# Drone_v1_0.net
KiCad netlist of a schematic drawn in Altium Designer
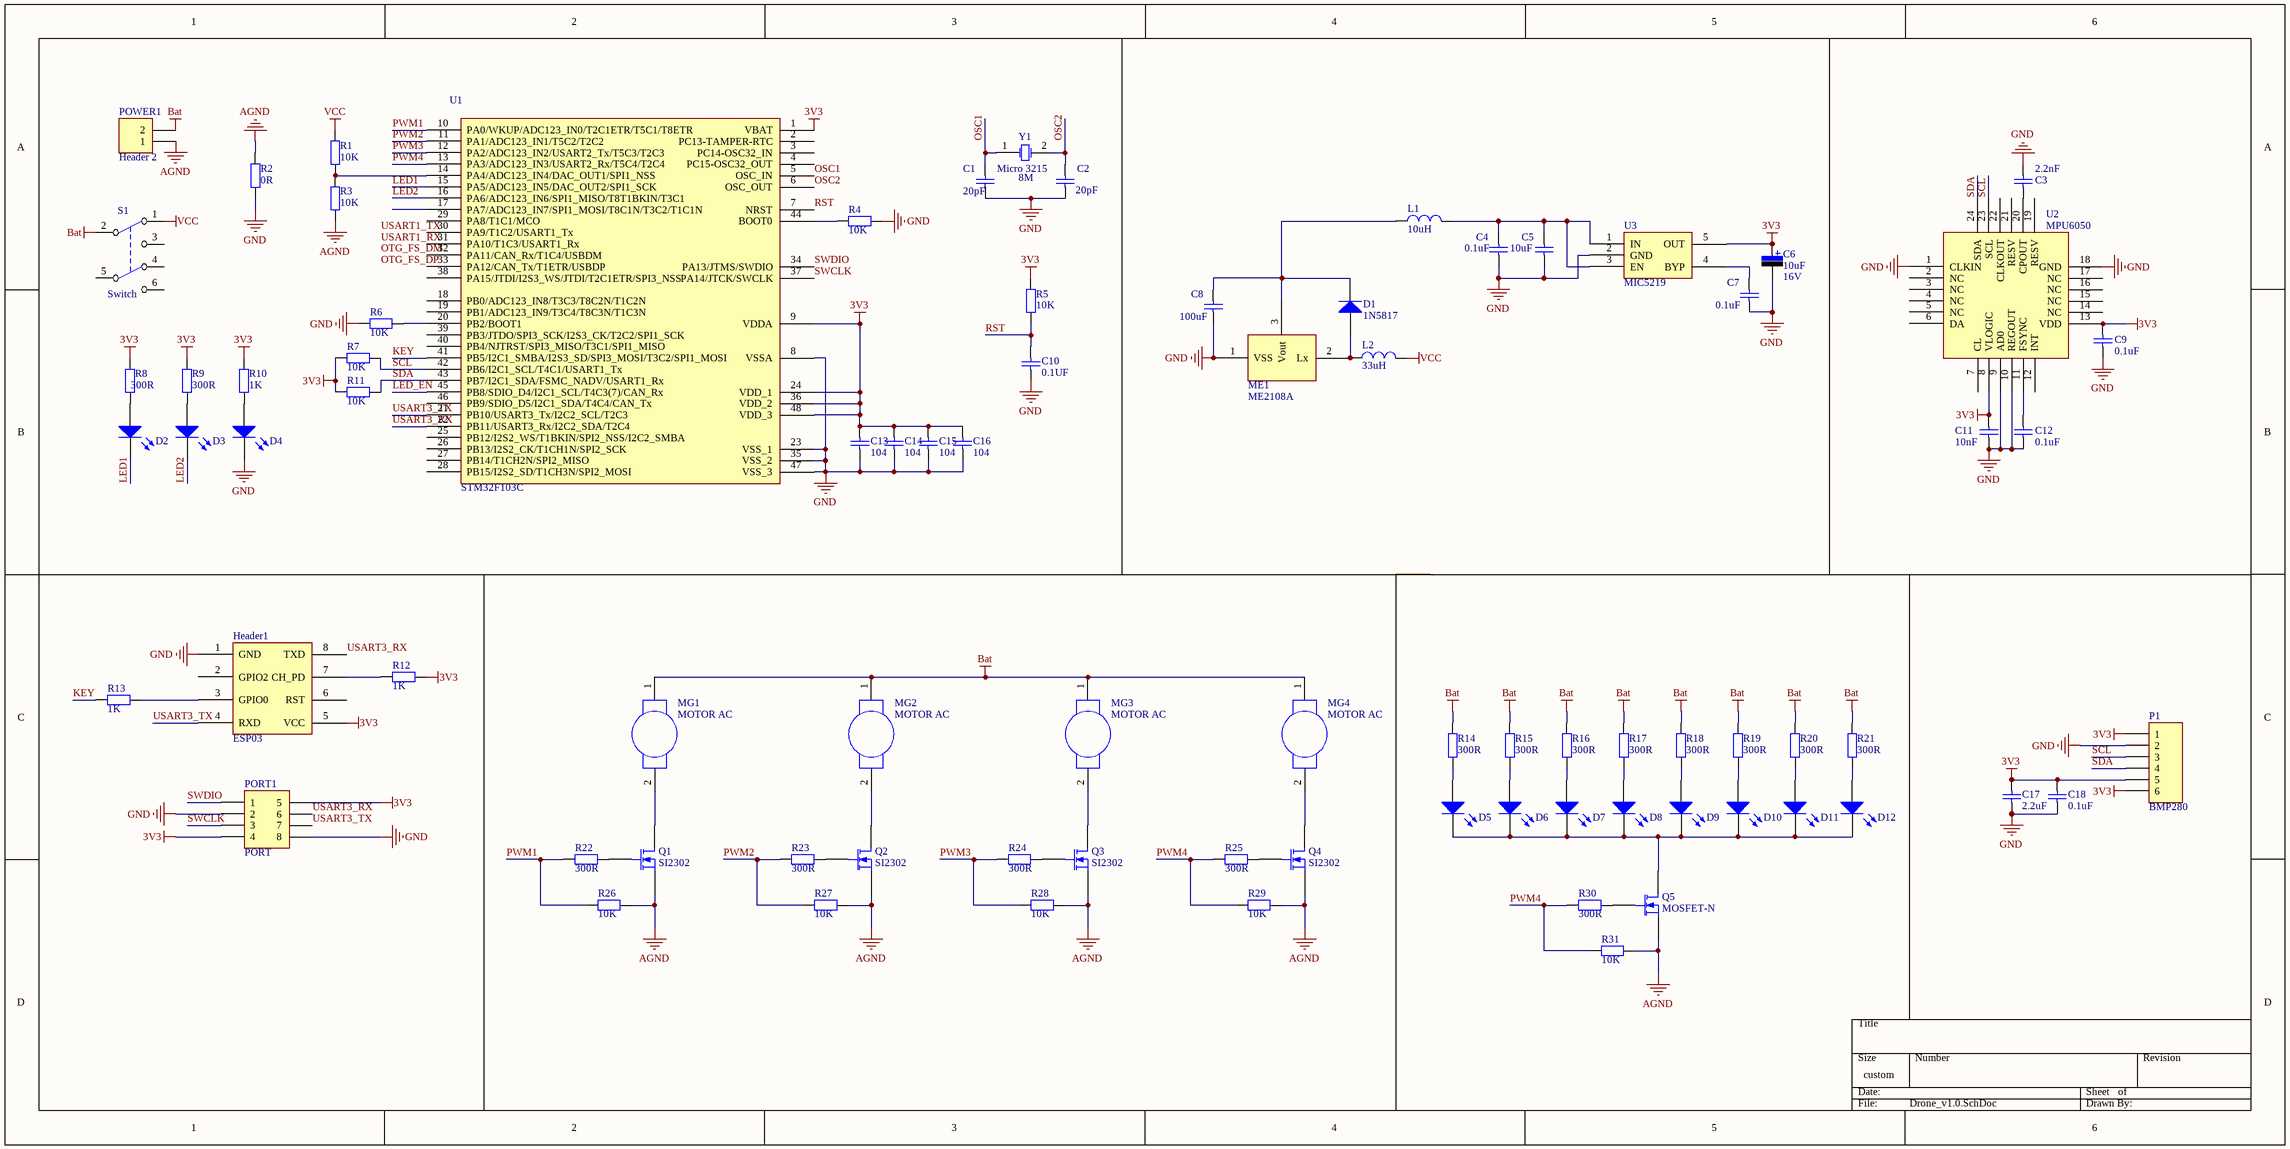
[diagram p0: Drone_v1.0.SchDoc]

(export (version "E")
  (design (tool "Eeschema 10.0.6"))
  (components
    (comp (ref "C1")
      (value "20pF")
      (footprint "0805-2")
      (description "Capacitor")
      (fields (field (name "Comment") "0402 12pF") (field (name "PUBLISHER") "Altium Limited"))
      (libsource (lib "Miscellaneous Devices") (part "Cap"))
    )
    (comp (ref "C2")
      (value "20pF")
      (footprint "0805-2")
      (description "Capacitor")
      (fields (field (name "Comment") "0402 12pF") (field (name "PUBLISHER") "Altium Limited"))
      (libsource (lib "Miscellaneous Devices") (part "Cap"))
    )
    (comp (ref "C3")
      (value "0402 12pF")
      (footprint "0805-2")
      (description "Capacitor")
      (fields (field (name "50V") "2.2nF") (field (name "PUBLISHER") "Altium Limited"))
      (libsource (lib "Miscellaneous Devices") (part "Cap"))
    )
    (comp (ref "C4")
      (value "0.1uF")
      (footprint "0805-2")
      (description "Capacitor")
      (fields (field (name "Comment") "0402 12pF") (field (name "PUBLISHER") "Altium Limited"))
      (libsource (lib "Miscellaneous Devices") (part "Cap"))
    )
    (comp (ref "C5")
      (value "10uF")
      (footprint "0805-2")
      (description "Capacitor")
      (fields (field (name "Comment") "0402 12pF") (field (name "PUBLISHER") "Altium Limited"))
      (libsource (lib "Miscellaneous Devices") (part "Cap"))
    )
    (comp (ref "C6")
      (value "10uF")
      (footprint "1206")
      (description "极性电解电容")
      (fields
        (field (name "VOL") "16V")
        (field (name "Comment") "Cap Pol")
        (field (name "PUBLISHER") "Altium Limited")
      )
      (libsource (lib "Fszhang") (part "Cap Pol"))
    )
    (comp (ref "C7")
      (value "0402 12pF")
      (footprint "0805-2")
      (description "Capacitor")
      (fields (field (name "50V") "0.1uF") (field (name "PUBLISHER") "Altium Limited"))
      (libsource (lib "Miscellaneous Devices") (part "Cap"))
    )
    (comp (ref "C8")
      (value "100uF")
      (footprint "0805-2")
      (description "Capacitor")
      (fields (field (name "Comment") "0402 12pF") (field (name "PUBLISHER") "Altium Limited"))
      (libsource (lib "Miscellaneous Devices") (part "Cap"))
    )
    (comp (ref "C9")
      (value "0402 12pF")
      (footprint "0805-2")
      (description "Capacitor")
      (fields (field (name "50V") "0.1uF") (field (name "PUBLISHER") "Altium Limited"))
      (libsource (lib "Miscellaneous Devices") (part "Cap"))
    )
    (comp (ref "C10")
      (value "0.1UF")
      (footprint "0805-2")
      (description "无极性电容")
      (fields (field (name "Comment") "Cap") (field (name "PUBLISHER") "Altium Limited"))
      (libsource (lib "Fszhang") (part "Cap"))
    )
    (comp (ref "C11")
      (value "0402 12pF")
      (footprint "0805-2")
      (description "Capacitor")
      (fields (field (name "50V") "10nF") (field (name "PUBLISHER") "Altium Limited"))
      (libsource (lib "Miscellaneous Devices") (part "Cap"))
    )
    (comp (ref "C12")
      (value "0402 12pF")
      (footprint "0805-2")
      (description "Capacitor")
      (fields (field (name "50V") "0.1uF") (field (name "PUBLISHER") "Altium Limited"))
      (libsource (lib "Miscellaneous Devices") (part "Cap"))
    )
    (comp (ref "C13")
      (value "104")
      (footprint "0805-2")
      (description "无极性电容")
      (fields (field (name "Comment") "Cap") (field (name "PUBLISHER") "Altium Limited"))
      (libsource (lib "Fszhang") (part "Cap"))
    )
    (comp (ref "C14")
      (value "104")
      (footprint "0805-2")
      (description "无极性电容")
      (fields (field (name "Comment") "Cap") (field (name "PUBLISHER") "Altium Limited"))
      (libsource (lib "Fszhang") (part "Cap"))
    )
    (comp (ref "C15")
      (value "104")
      (footprint "0805-2")
      (description "无极性电容")
      (fields (field (name "Comment") "Cap") (field (name "PUBLISHER") "Altium Limited"))
      (libsource (lib "Fszhang") (part "Cap"))
    )
    (comp (ref "C16")
      (value "104")
      (footprint "0805-2")
      (description "无极性电容")
      (fields (field (name "Comment") "Cap") (field (name "PUBLISHER") "Altium Limited"))
      (libsource (lib "Fszhang") (part "Cap"))
    )
    (comp (ref "C17")
      (value "0402 12pF")
      (footprint "0805-2")
      (description "Capacitor")
      (fields (field (name "50V") "2.2uF") (field (name "PUBLISHER") "Altium Limited"))
      (libsource (lib "Miscellaneous Devices") (part "Cap"))
    )
    (comp (ref "C18")
      (value "0402 12pF")
      (footprint "0805-2")
      (description "Capacitor")
      (fields (field (name "50V") "0.1uF") (field (name "PUBLISHER") "Altium Limited"))
      (libsource (lib "Miscellaneous Devices") (part "Cap"))
    )
    (comp (ref "D1")
      (value "Diode")
      (footprint "DIODE-1206")
      (description "二极管")
      (fields (field (name "TYPE") "1N5817") (field (name "PUBLISHER") "Altium Limited"))
      (libsource (lib "Fszhang") (part "Diode"))
    )
    (comp (ref "D2")
      (value "LED0")
      (footprint "LED_0805")
      (description "发光二极管")
      (fields (field (name "PUBLISHER") "Altium Limited"))
      (libsource (lib "Fszhang") (part "LED0"))
    )
    (comp (ref "D3")
      (value "LED0")
      (footprint "LED_0805")
      (description "发光二极管")
      (fields (field (name "PUBLISHER") "Altium Limited"))
      (libsource (lib "Fszhang") (part "LED0"))
    )
    (comp (ref "D4")
      (value "LED0")
      (footprint "LED_0805")
      (description "发光二极管")
      (fields (field (name "PUBLISHER") "Altium Limited"))
      (libsource (lib "Fszhang") (part "LED0"))
    )
    (comp (ref "D5")
      (value "LED0")
      (footprint "LED_0805")
      (description "发光二极管")
      (fields (field (name "PUBLISHER") "Altium Limited"))
      (libsource (lib "Fszhang") (part "LED0"))
    )
    (comp (ref "D6")
      (value "LED0")
      (footprint "LED_0805")
      (description "发光二极管")
      (fields (field (name "PUBLISHER") "Altium Limited"))
      (libsource (lib "Fszhang") (part "LED0"))
    )
    (comp (ref "D7")
      (value "LED0")
      (footprint "LED_0805")
      (description "发光二极管")
      (fields (field (name "PUBLISHER") "Altium Limited"))
      (libsource (lib "Fszhang") (part "LED0"))
    )
    (comp (ref "D8")
      (value "LED0")
      (footprint "LED_0805")
      (description "发光二极管")
      (fields (field (name "PUBLISHER") "Altium Limited"))
      (libsource (lib "Fszhang") (part "LED0"))
    )
    (comp (ref "D9")
      (value "LED0")
      (footprint "LED_0805")
      (description "发光二极管")
      (fields (field (name "PUBLISHER") "Altium Limited"))
      (libsource (lib "Fszhang") (part "LED0"))
    )
    (comp (ref "D10")
      (value "LED0")
      (footprint "LED_0805")
      (description "发光二极管")
      (fields (field (name "PUBLISHER") "Altium Limited"))
      (libsource (lib "Fszhang") (part "LED0"))
    )
    (comp (ref "D11")
      (value "LED0")
      (footprint "LED_0805")
      (description "发光二极管")
      (fields (field (name "PUBLISHER") "Altium Limited"))
      (libsource (lib "Fszhang") (part "LED0"))
    )
    (comp (ref "D12")
      (value "LED0")
      (footprint "LED_0805")
      (description "发光二极管")
      (fields (field (name "PUBLISHER") "Altium Limited"))
      (libsource (lib "Fszhang") (part "LED0"))
    )
    (comp (ref "Header1")
      (value "ESP03")
      (footprint "PCBComponent_1")
      (libsource (lib "Header4") (part "Hearder"))
    )
    (comp (ref "L1")
      (value "10uH")
      (footprint "0805-1")
      (description "电感")
      (fields (field (name "Comment") "Inductor") (field (name "PUBLISHER") "Altium Limited"))
      (libsource (lib "Fszhang") (part "Inductor"))
    )
    (comp (ref "L2")
      (value "33uH")
      (footprint "0805-1")
      (description "电感")
      (fields (field (name "Comment") "Inductor") (field (name "PUBLISHER") "Altium Limited"))
      (libsource (lib "Fszhang") (part "Inductor"))
    )
    (comp (ref "ME1") (value "ME2108A") (footprint "SOT-89") (libsource (lib "ME2108A") (part "ME2108A")))
    (comp (ref "MG1") (value "MOTOR AC") (footprint "Motor") (libsource (lib "杂元件库") (part "MOTOR AC")))
    (comp (ref "MG2") (value "MOTOR AC") (footprint "Motor") (libsource (lib "杂元件库") (part "MOTOR AC")))
    (comp (ref "MG3") (value "MOTOR AC") (footprint "Motor") (libsource (lib "杂元件库") (part "MOTOR AC")))
    (comp (ref "MG4") (value "MOTOR AC") (footprint "Motor") (libsource (lib "杂元件库") (part "MOTOR AC")))
    (comp (ref "P1")
      (value "BMP280")
      (footprint "HDR1X6")
      (description "Header, 6-Pin")
      (fields (field (name "PUBLISHER") "Altium Limited"))
      (libsource (lib "Miscellaneous Connectors") (part "Header 6"))
    )
    (comp (ref "PORT1")
      (value "PORT")
      (footprint "HDR2X4_CEN")
      (description "Header, 4-Pin, Dual row")
      (fields (field (name "PUBLISHER") "Altium Limited"))
      (libsource (lib "Miscellaneous Connectors") (part "Header 4X2A"))
    )
    (comp (ref "POWER1")
      (value "Header 2")
      (footprint "HDR1X2")
      (description "Header, 2-Pin")
      (fields (field (name "PUBLISHER") "Altium Limited"))
      (libsource (lib "Miscellaneous Connectors") (part "Header 2"))
    )
    (comp (ref "Q1")
      (value "SI2302")
      (footprint "SOT-23")
      (description "N-Channel MOSFET")
      (fields (field (name "PUBLISHER") "Altium Limited"))
      (libsource (lib "Miscellaneous Devices") (part "MOSFET-N"))
    )
    (comp (ref "Q2")
      (value "SI2302")
      (footprint "SOT-23")
      (description "N-Channel MOSFET")
      (fields (field (name "PUBLISHER") "Altium Limited"))
      (libsource (lib "Miscellaneous Devices") (part "MOSFET-N"))
    )
    (comp (ref "Q3")
      (value "SI2302")
      (footprint "SOT-23")
      (description "N-Channel MOSFET")
      (fields (field (name "PUBLISHER") "Altium Limited"))
      (libsource (lib "Miscellaneous Devices") (part "MOSFET-N"))
    )
    (comp (ref "Q4")
      (value "SI2302")
      (footprint "SOT-23")
      (description "N-Channel MOSFET")
      (fields (field (name "PUBLISHER") "Altium Limited"))
      (libsource (lib "Miscellaneous Devices") (part "MOSFET-N"))
    )
    (comp (ref "Q5")
      (value "MOSFET-N")
      (footprint "SOT-23")
      (description "N-Channel MOSFET")
      (fields (field (name "PUBLISHER") "Altium Limited"))
      (libsource (lib "Miscellaneous Devices") (part "MOSFET-N"))
    )
    (comp (ref "R1")
      (value "10K")
      (footprint "0805-2")
      (description "贴片电阻")
      (fields (field (name "Comment") "Res1") (field (name "PUBLISHER") "Altium Limited"))
      (libsource (lib "") (part "Res1_2"))
    )
    (comp (ref "R2")
      (value "0R")
      (footprint "0805-2")
      (description "贴片电阻")
      (fields (field (name "Comment") "Res1") (field (name "PUBLISHER") "Altium Limited"))
      (libsource (lib "") (part "Res1_2"))
    )
    (comp (ref "R3")
      (value "10K")
      (footprint "0805-2")
      (description "贴片电阻")
      (fields (field (name "Comment") "Res1") (field (name "PUBLISHER") "Altium Limited"))
      (libsource (lib "") (part "Res1_3"))
    )
    (comp (ref "R4")
      (value "10K")
      (footprint "0805-2")
      (description "贴片电阻")
      (fields (field (name "Comment") "Res1") (field (name "PUBLISHER") "Altium Limited"))
      (libsource (lib "Fszhang") (part "Res1"))
    )
    (comp (ref "R5")
      (value "10K")
      (footprint "0805-2")
      (description "贴片电阻")
      (fields (field (name "Comment") "Res1") (field (name "PUBLISHER") "Altium Limited"))
      (libsource (lib "") (part "Res1_2"))
    )
    (comp (ref "R6")
      (value "10K")
      (footprint "0805-2")
      (description "贴片电阻")
      (fields (field (name "Comment") "Res1") (field (name "PUBLISHER") "Altium Limited"))
      (libsource (lib "") (part "Res1_1"))
    )
    (comp (ref "R7")
      (value "10K")
      (footprint "0805-2")
      (description "贴片电阻")
      (fields (field (name "Comment") "Res1") (field (name "PUBLISHER") "Altium Limited"))
      (libsource (lib "") (part "Res1_1"))
    )
    (comp (ref "R8")
      (value "300R")
      (footprint "0805-2")
      (description "贴片电阻")
      (fields (field (name "Comment") "Res1") (field (name "PUBLISHER") "Altium Limited"))
      (libsource (lib "") (part "Res1_2"))
    )
    (comp (ref "R9")
      (value "300R")
      (footprint "0805-2")
      (description "贴片电阻")
      (fields (field (name "Comment") "Res1") (field (name "PUBLISHER") "Altium Limited"))
      (libsource (lib "") (part "Res1_2"))
    )
    (comp (ref "R10")
      (value "1K")
      (footprint "0805-2")
      (description "贴片电阻")
      (fields (field (name "Comment") "Res1") (field (name "PUBLISHER") "Altium Limited"))
      (libsource (lib "") (part "Res1_2"))
    )
    (comp (ref "R11")
      (value "10K")
      (footprint "0805-2")
      (description "贴片电阻")
      (fields (field (name "Comment") "Res1") (field (name "PUBLISHER") "Altium Limited"))
      (libsource (lib "") (part "Res1_1"))
    )
    (comp (ref "R12")
      (value "1K")
      (footprint "0805-2")
      (description "贴片电阻")
      (fields (field (name "Comment") "Res1") (field (name "PUBLISHER") "Altium Limited"))
      (libsource (lib "") (part "Res1_1"))
    )
    (comp (ref "R13")
      (value "1K")
      (footprint "0805-2")
      (description "贴片电阻")
      (fields (field (name "Comment") "Res1") (field (name "PUBLISHER") "Altium Limited"))
      (libsource (lib "") (part "Res1_1"))
    )
    (comp (ref "R14")
      (value "300R")
      (footprint "0805-2")
      (description "贴片电阻")
      (fields (field (name "Comment") "Res1") (field (name "PUBLISHER") "Altium Limited"))
      (libsource (lib "") (part "Res1_3"))
    )
    (comp (ref "R15")
      (value "300R")
      (footprint "0805-2")
      (description "贴片电阻")
      (fields (field (name "Comment") "Res1") (field (name "PUBLISHER") "Altium Limited"))
      (libsource (lib "") (part "Res1_3"))
    )
    (comp (ref "R16")
      (value "300R")
      (footprint "0805-2")
      (description "贴片电阻")
      (fields (field (name "Comment") "Res1") (field (name "PUBLISHER") "Altium Limited"))
      (libsource (lib "") (part "Res1_3"))
    )
    (comp (ref "R17")
      (value "300R")
      (footprint "0805-2")
      (description "贴片电阻")
      (fields (field (name "Comment") "Res1") (field (name "PUBLISHER") "Altium Limited"))
      (libsource (lib "") (part "Res1_3"))
    )
    (comp (ref "R18")
      (value "300R")
      (footprint "0805-2")
      (description "贴片电阻")
      (fields (field (name "Comment") "Res1") (field (name "PUBLISHER") "Altium Limited"))
      (libsource (lib "") (part "Res1_3"))
    )
    (comp (ref "R19")
      (value "300R")
      (footprint "0805-2")
      (description "贴片电阻")
      (fields (field (name "Comment") "Res1") (field (name "PUBLISHER") "Altium Limited"))
      (libsource (lib "") (part "Res1_3"))
    )
    (comp (ref "R20")
      (value "300R")
      (footprint "0805-2")
      (description "贴片电阻")
      (fields (field (name "Comment") "Res1") (field (name "PUBLISHER") "Altium Limited"))
      (libsource (lib "") (part "Res1_3"))
    )
    (comp (ref "R21")
      (value "300R")
      (footprint "0805-2")
      (description "贴片电阻")
      (fields (field (name "Comment") "Res1") (field (name "PUBLISHER") "Altium Limited"))
      (libsource (lib "") (part "Res1_3"))
    )
    (comp (ref "R22")
      (value "300R")
      (footprint "0805-2")
      (description "贴片电阻")
      (fields (field (name "Comment") "Res1") (field (name "PUBLISHER") "Altium Limited"))
      (libsource (lib "Fszhang") (part "Res1"))
    )
    (comp (ref "R23")
      (value "300R")
      (footprint "0805-2")
      (description "贴片电阻")
      (fields (field (name "Comment") "Res1") (field (name "PUBLISHER") "Altium Limited"))
      (libsource (lib "Fszhang") (part "Res1"))
    )
    (comp (ref "R24")
      (value "300R")
      (footprint "0805-2")
      (description "贴片电阻")
      (fields (field (name "Comment") "Res1") (field (name "PUBLISHER") "Altium Limited"))
      (libsource (lib "Fszhang") (part "Res1"))
    )
    (comp (ref "R25")
      (value "300R")
      (footprint "0805-2")
      (description "贴片电阻")
      (fields (field (name "Comment") "Res1") (field (name "PUBLISHER") "Altium Limited"))
      (libsource (lib "Fszhang") (part "Res1"))
    )
    (comp (ref "R26")
      (value "10K")
      (footprint "0805-2")
      (description "贴片电阻")
      (fields (field (name "Comment") "Res1") (field (name "PUBLISHER") "Altium Limited"))
      (libsource (lib "Fszhang") (part "Res1"))
    )
    (comp (ref "R27")
      (value "10K")
      (footprint "0805-2")
      (description "贴片电阻")
      (fields (field (name "Comment") "Res1") (field (name "PUBLISHER") "Altium Limited"))
      (libsource (lib "Fszhang") (part "Res1"))
    )
    (comp (ref "R28")
      (value "10K")
      (footprint "0805-2")
      (description "贴片电阻")
      (fields (field (name "Comment") "Res1") (field (name "PUBLISHER") "Altium Limited"))
      (libsource (lib "Fszhang") (part "Res1"))
    )
    (comp (ref "R29")
      (value "10K")
      (footprint "0805-2")
      (description "贴片电阻")
      (fields (field (name "Comment") "Res1") (field (name "PUBLISHER") "Altium Limited"))
      (libsource (lib "Fszhang") (part "Res1"))
    )
    (comp (ref "R30")
      (value "300R")
      (footprint "0805-2")
      (description "贴片电阻")
      (fields (field (name "Comment") "Res1") (field (name "PUBLISHER") "Altium Limited"))
      (libsource (lib "Fszhang") (part "Res1"))
    )
    (comp (ref "R31")
      (value "10K")
      (footprint "0805-2")
      (description "贴片电阻")
      (fields (field (name "Comment") "Res1") (field (name "PUBLISHER") "Altium Limited"))
      (libsource (lib "Fszhang") (part "Res1"))
    )
    (comp (ref "S1") (value "Switch") (footprint "开关") (libsource (lib "开关") (part "双刀双柄开关")))
    (comp (ref "U1")
      (value "STM32F103C")
      (footprint "LQFP-48_M")
      (description "STM32单片机48引脚")
      (libsource (lib "Fszhang") (part "STM32F103C"))
    )
    (comp (ref "U2")
      (value "MPU6050")
      (footprint "QFN50P400X400X90-24N")
      (libsource (lib "MPU6050") (part "MPU6050"))
    )
    (comp (ref "U3") (value "MIC5219") (footprint "SOT25-5") (libsource (lib "MIC5219") (part "MIC5219")))
    (comp (ref "Y1")
      (value "Micro 3215")
      (footprint "XTAL5")
      (description "Crystal Oscillator")
      (fields (field (name "ALTIUM_VALUE") "8M"))
      (libsource (lib "Miscellaneous Devices") (part "XTAL"))
    )
  )
  (nets
    (net (code "1") (name "/KEY") (class "Default")
      (node (ref "R13") (pin "1") (pinfunction "1_1") (pintype "passive"))
      (node (ref "U1") (pin "41") (pinfunction "PB5/I2C1_SMBA/I2S3_SD/SPI3_MOSI/T3C2/SPI1_MOSI_41") (pintype "passive"))
    )
    (net (code "2") (name "/LED1") (class "Default")
      (node (ref "D2") (pin "2") (pinfunction "K_2") (pintype "passive"))
      (node (ref "U1") (pin "15") (pinfunction "PA5/ADC123_IN5/DAC_OUT2/SPI1_SCK_15") (pintype "passive"))
    )
    (net (code "3") (name "/LED2") (class "Default")
      (node (ref "D3") (pin "2") (pinfunction "K_2") (pintype "passive"))
      (node (ref "U1") (pin "16") (pinfunction "PA6/ADC123_IN6/SPI1_MISO/T8T1BKIN/T3C1_16") (pintype "passive"))
    )
    (net (code "4") (name "/LED_EN") (class "Default")
      (node (ref "U1") (pin "45") (pinfunction "PB8/SDIO_D4/I2C1_SCL/T4C3(7)/CAN_Rx_45") (pintype "passive"))
    )
    (net (code "5") (name "/OSC1") (class "Default")
      (node (ref "C1") (pin "1") (pinfunction "1_1") (pintype "passive"))
      (node (ref "U1") (pin "5") (pinfunction "OSC_IN_5") (pintype "passive"))
      (node (ref "Y1") (pin "1") (pinfunction "OSC1_1") (pintype "passive"))
    )
    (net (code "6") (name "/OSC2") (class "Default")
      (node (ref "C2") (pin "2") (pinfunction "2_2") (pintype "passive"))
      (node (ref "U1") (pin "6") (pinfunction "OSC_OUT_6") (pintype "passive"))
      (node (ref "Y1") (pin "2") (pinfunction "OSC2_2") (pintype "passive"))
    )
    (net (code "9") (name "/PWM1") (class "Default")
      (node (ref "R22") (pin "2") (pinfunction "2_2") (pintype "passive"))
      (node (ref "R26") (pin "2") (pinfunction "2_2") (pintype "passive"))
      (node (ref "U1") (pin "10") (pinfunction "PA0/WKUP/ADC123_IN0/T2C1ETR/T5C1/T8ETR_10") (pintype "passive"))
    )
    (net (code "10") (name "/PWM2") (class "Default")
      (node (ref "R23") (pin "2") (pinfunction "2_2") (pintype "passive"))
      (node (ref "R27") (pin "2") (pinfunction "2_2") (pintype "passive"))
      (node (ref "U1") (pin "11") (pinfunction "PA1/ADC123_IN1/T5C2/T2C2_11") (pintype "passive"))
    )
    (net (code "11") (name "/PWM3") (class "Default")
      (node (ref "R24") (pin "2") (pinfunction "2_2") (pintype "passive"))
      (node (ref "R28") (pin "2") (pinfunction "2_2") (pintype "passive"))
      (node (ref "U1") (pin "12") (pinfunction "PA2/ADC123_IN2/USART2_Tx/T5C3/T2C3_12") (pintype "passive"))
    )
    (net (code "12") (name "/PWM4") (class "Default")
      (node (ref "R25") (pin "2") (pinfunction "2_2") (pintype "passive"))
      (node (ref "R29") (pin "2") (pinfunction "2_2") (pintype "passive"))
      (node (ref "R30") (pin "2") (pinfunction "2_2") (pintype "passive"))
      (node (ref "R31") (pin "2") (pinfunction "2_2") (pintype "passive"))
      (node (ref "U1") (pin "13") (pinfunction "PA3/ADC123_IN3/USART2_Rx/T5C4/T2C4_13") (pintype "passive"))
    )
    (net (code "13") (name "/RST") (class "Default")
      (node (ref "C10") (pin "1") (pinfunction "1_1") (pintype "passive"))
      (node (ref "R5") (pin "1") (pinfunction "1_1") (pintype "passive"))
      (node (ref "U1") (pin "7") (pinfunction "NRST_7") (pintype "passive"))
    )
    (net (code "14") (name "/SCL") (class "Default")
      (node (ref "P1") (pin "3") (pinfunction "3_3") (pintype "passive"))
      (node (ref "R7") (pin "2") (pinfunction "2_2") (pintype "passive"))
      (node (ref "U1") (pin "42") (pinfunction "PB6/I2C1_SCL/T4C1/USART1_Tx_42") (pintype "passive"))
      (node (ref "U2") (pin "23") (pinfunction "SCL_23") (pintype "passive"))
    )
    (net (code "15") (name "/SDA") (class "Default")
      (node (ref "P1") (pin "4") (pinfunction "4_4") (pintype "passive"))
      (node (ref "R11") (pin "2") (pinfunction "2_2") (pintype "passive"))
      (node (ref "U1") (pin "43") (pinfunction "PB7/I2C1_SDA/FSMC_NADV/USART1_Rx_43") (pintype "passive"))
      (node (ref "U2") (pin "24") (pinfunction "SDA_24") (pintype "passive"))
    )
    (net (code "16") (name "/SWCLK") (class "Default")
      (node (ref "PORT1") (pin "3") (pinfunction "3_3") (pintype "passive"))
      (node (ref "U1") (pin "37") (pinfunction "PA14/JTCK/SWCLK_37") (pintype "passive"))
    )
    (net (code "17") (name "/SWDIO") (class "Default")
      (node (ref "PORT1") (pin "1") (pinfunction "1_1") (pintype "passive"))
      (node (ref "U1") (pin "34") (pinfunction "PA13/JTMS/SWDIO_34") (pintype "passive"))
    )
    (net (code "20") (name "/USART3_RX") (class "Default")
      (node (ref "Header1") (pin "8") (pinfunction "TXD_8") (pintype "passive"))
      (node (ref "PORT1") (pin "6") (pinfunction "6_6") (pintype "passive"))
      (node (ref "U1") (pin "22") (pinfunction "PB11/USART3_Rx/I2C2_SDA/T2C4_22") (pintype "passive"))
    )
    (net (code "21") (name "/USART3_TX") (class "Default")
      (node (ref "Header1") (pin "4") (pinfunction "RXD_4") (pintype "passive"))
      (node (ref "PORT1") (pin "7") (pinfunction "7_7") (pintype "passive"))
      (node (ref "U1") (pin "21") (pinfunction "PB10/USART3_Tx/I2C2_SCL/T2C3_21") (pintype "passive"))
    )
    (net (code "22") (name "3V3") (class "Default")
      (node (ref "C11") (pin "1") (pinfunction "1_1") (pintype "passive"))
      (node (ref "C13") (pin "2") (pinfunction "2_2") (pintype "passive"))
      (node (ref "C14") (pin "2") (pinfunction "2_2") (pintype "passive"))
      (node (ref "C15") (pin "2") (pinfunction "2_2") (pintype "passive"))
      (node (ref "C16") (pin "2") (pinfunction "2_2") (pintype "passive"))
      (node (ref "C17") (pin "1") (pinfunction "1_1") (pintype "passive"))
      (node (ref "C18") (pin "1") (pinfunction "1_1") (pintype "passive"))
      (node (ref "C6") (pin "1") (pinfunction "1_1") (pintype "passive"))
      (node (ref "C9") (pin "1") (pinfunction "1_1") (pintype "passive"))
      (node (ref "Header1") (pin "5") (pinfunction "VCC_5") (pintype "passive"))
      (node (ref "P1") (pin "1") (pinfunction "1_1") (pintype "passive"))
      (node (ref "P1") (pin "5") (pinfunction "5_5") (pintype "passive"))
      (node (ref "P1") (pin "6") (pinfunction "6_6") (pintype "passive"))
      (node (ref "PORT1") (pin "4") (pinfunction "4_4") (pintype "passive"))
      (node (ref "PORT1") (pin "5") (pinfunction "5_5") (pintype "passive"))
      (node (ref "R10") (pin "2") (pinfunction "2_2") (pintype "passive"))
      (node (ref "R11") (pin "1") (pinfunction "1_1") (pintype "passive"))
      (node (ref "R12") (pin "2") (pinfunction "2_2") (pintype "passive"))
      (node (ref "R5") (pin "2") (pinfunction "2_2") (pintype "passive"))
      (node (ref "R7") (pin "1") (pinfunction "1_1") (pintype "passive"))
      (node (ref "R8") (pin "2") (pinfunction "2_2") (pintype "passive"))
      (node (ref "R9") (pin "2") (pinfunction "2_2") (pintype "passive"))
      (node (ref "U1") (pin "1") (pinfunction "VBAT_1") (pintype "passive"))
      (node (ref "U1") (pin "24") (pinfunction "VDD_1_24") (pintype "passive"))
      (node (ref "U1") (pin "36") (pinfunction "VDD_2_36") (pintype "passive"))
      (node (ref "U1") (pin "48") (pinfunction "VDD_3_48") (pintype "passive"))
      (node (ref "U1") (pin "9") (pinfunction "VDDA_9") (pintype "passive"))
      (node (ref "U2") (pin "13") (pinfunction "VDD_13") (pintype "passive"))
      (node (ref "U2") (pin "8") (pinfunction "VLOGIC_8") (pintype "passive"))
      (node (ref "U3") (pin "5") (pinfunction "OUT_5") (pintype "passive"))
    )
    (net (code "23") (name "AGND") (class "Default")
      (node (ref "POWER1") (pin "1") (pinfunction "1_1") (pintype "passive"))
      (node (ref "Q1") (pin "3") (pinfunction "S_3") (pintype "passive"))
      (node (ref "Q2") (pin "3") (pinfunction "S_3") (pintype "passive"))
      (node (ref "Q3") (pin "3") (pinfunction "S_3") (pintype "passive"))
      (node (ref "Q4") (pin "3") (pinfunction "S_3") (pintype "passive"))
      (node (ref "Q5") (pin "3") (pinfunction "S_3") (pintype "passive"))
      (node (ref "R2") (pin "2") (pinfunction "2_2") (pintype "passive"))
      (node (ref "R26") (pin "1") (pinfunction "1_1") (pintype "passive"))
      (node (ref "R27") (pin "1") (pinfunction "1_1") (pintype "passive"))
      (node (ref "R28") (pin "1") (pinfunction "1_1") (pintype "passive"))
      (node (ref "R29") (pin "1") (pinfunction "1_1") (pintype "passive"))
      (node (ref "R3") (pin "2") (pinfunction "2_2") (pintype "passive"))
      (node (ref "R31") (pin "1") (pinfunction "1_1") (pintype "passive"))
    )
    (net (code "24") (name "Bat") (class "Default")
      (node (ref "MG1") (pin "1") (pinfunction "1_1") (pintype "passive"))
      (node (ref "MG2") (pin "1") (pinfunction "1_1") (pintype "passive"))
      (node (ref "MG3") (pin "1") (pinfunction "1_1") (pintype "passive"))
      (node (ref "MG4") (pin "1") (pinfunction "1_1") (pintype "passive"))
      (node (ref "POWER1") (pin "2") (pinfunction "2_2") (pintype "passive"))
      (node (ref "R14") (pin "1") (pinfunction "1_1") (pintype "passive"))
      (node (ref "R15") (pin "1") (pinfunction "1_1") (pintype "passive"))
      (node (ref "R16") (pin "1") (pinfunction "1_1") (pintype "passive"))
      (node (ref "R17") (pin "1") (pinfunction "1_1") (pintype "passive"))
      (node (ref "R18") (pin "1") (pinfunction "1_1") (pintype "passive"))
      (node (ref "R19") (pin "1") (pinfunction "1_1") (pintype "passive"))
      (node (ref "R20") (pin "1") (pinfunction "1_1") (pintype "passive"))
      (node (ref "R21") (pin "1") (pinfunction "1_1") (pintype "passive"))
      (node (ref "S1") (pin "2") (pinfunction "COMMON1_2") (pintype "passive"))
    )
    (net (code "25") (name "GND") (class "Default")
      (node (ref "C1") (pin "2") (pinfunction "2_2") (pintype "passive"))
      (node (ref "C10") (pin "2") (pinfunction "2_2") (pintype "passive"))
      (node (ref "C11") (pin "2") (pinfunction "2_2") (pintype "passive"))
      (node (ref "C12") (pin "2") (pinfunction "2_2") (pintype "passive"))
      (node (ref "C13") (pin "1") (pinfunction "1_1") (pintype "passive"))
      (node (ref "C14") (pin "1") (pinfunction "1_1") (pintype "passive"))
      (node (ref "C15") (pin "1") (pinfunction "1_1") (pintype "passive"))
      (node (ref "C16") (pin "1") (pinfunction "1_1") (pintype "passive"))
      (node (ref "C17") (pin "2") (pinfunction "2_2") (pintype "passive"))
      (node (ref "C18") (pin "2") (pinfunction "2_2") (pintype "passive"))
      (node (ref "C2") (pin "1") (pinfunction "1_1") (pintype "passive"))
      (node (ref "C3") (pin "1") (pinfunction "1_1") (pintype "passive"))
      (node (ref "C4") (pin "2") (pinfunction "2_2") (pintype "passive"))
      (node (ref "C5") (pin "2") (pinfunction "2_2") (pintype "passive"))
      (node (ref "C6") (pin "2") (pinfunction "2_2") (pintype "passive"))
      (node (ref "C7") (pin "2") (pinfunction "2_2") (pintype "passive"))
      (node (ref "C8") (pin "2") (pinfunction "2_2") (pintype "passive"))
      (node (ref "C9") (pin "2") (pinfunction "2_2") (pintype "passive"))
      (node (ref "D4") (pin "2") (pinfunction "K_2") (pintype "passive"))
      (node (ref "Header1") (pin "1") (pinfunction "GND_1") (pintype "passive"))
      (node (ref "ME1") (pin "1") (pinfunction "VSS_1") (pintype "passive"))
      (node (ref "P1") (pin "2") (pinfunction "2_2") (pintype "passive"))
      (node (ref "PORT1") (pin "2") (pinfunction "2_2") (pintype "passive"))
      (node (ref "PORT1") (pin "8") (pinfunction "8_8") (pintype "passive"))
      (node (ref "R2") (pin "1") (pinfunction "1_1") (pintype "passive"))
      (node (ref "R4") (pin "1") (pinfunction "1_1") (pintype "passive"))
      (node (ref "R6") (pin "1") (pinfunction "1_1") (pintype "passive"))
      (node (ref "U1") (pin "23") (pinfunction "VSS_1_23") (pintype "passive"))
      (node (ref "U1") (pin "35") (pinfunction "VSS_2_35") (pintype "passive"))
      (node (ref "U1") (pin "47") (pinfunction "VSS_3_47") (pintype "passive"))
      (node (ref "U1") (pin "8") (pinfunction "VSSA_8") (pintype "passive"))
      (node (ref "U2") (pin "1") (pinfunction "CLKIN_1") (pintype "passive"))
      (node (ref "U2") (pin "10") (pinfunction "REGOUT_10") (pintype "passive"))
      (node (ref "U2") (pin "18") (pinfunction "GND_18") (pintype "passive"))
      (node (ref "U2") (pin "9") (pinfunction "AD0_9") (pintype "passive"))
      (node (ref "U3") (pin "2") (pinfunction "GND_2") (pintype "passive"))
    )
    (net (code "26") (name "Net-(D1-A)") (class "Default")
      (node (ref "D1") (pin "1") (pinfunction "A_1") (pintype "passive"))
      (node (ref "L2") (pin "1") (pinfunction "1_1") (pintype "passive"))
      (node (ref "ME1") (pin "2") (pinfunction "Lx_2") (pintype "passive"))
    )
    (net (code "27") (name "Net-(D1-K)") (class "Default")
      (node (ref "C8") (pin "1") (pinfunction "1_1") (pintype "passive"))
      (node (ref "D1") (pin "2") (pinfunction "K_2") (pintype "passive"))
      (node (ref "L1") (pin "1") (pinfunction "1_1") (pintype "passive"))
      (node (ref "ME1") (pin "3") (pinfunction "Vout_3") (pintype "passive"))
    )
    (net (code "28") (name "Net-(D2-A)") (class "Default")
      (node (ref "D2") (pin "1") (pinfunction "A_1") (pintype "passive"))
      (node (ref "R8") (pin "1") (pinfunction "1_1") (pintype "passive"))
    )
    (net (code "29") (name "Net-(D3-A)") (class "Default")
      (node (ref "D3") (pin "1") (pinfunction "A_1") (pintype "passive"))
      (node (ref "R9") (pin "1") (pinfunction "1_1") (pintype "passive"))
    )
    (net (code "30") (name "Net-(D4-A)") (class "Default")
      (node (ref "D4") (pin "1") (pinfunction "A_1") (pintype "passive"))
      (node (ref "R10") (pin "1") (pinfunction "1_1") (pintype "passive"))
    )
    (net (code "31") (name "Net-(D5-A)") (class "Default")
      (node (ref "D5") (pin "1") (pinfunction "A_1") (pintype "passive"))
      (node (ref "R14") (pin "2") (pinfunction "2_2") (pintype "passive"))
    )
    (net (code "32") (name "Net-(D6-A)") (class "Default")
      (node (ref "D6") (pin "1") (pinfunction "A_1") (pintype "passive"))
      (node (ref "R15") (pin "2") (pinfunction "2_2") (pintype "passive"))
    )
    (net (code "33") (name "Net-(D7-A)") (class "Default")
      (node (ref "D7") (pin "1") (pinfunction "A_1") (pintype "passive"))
      (node (ref "R16") (pin "2") (pinfunction "2_2") (pintype "passive"))
    )
    (net (code "34") (name "Net-(D8-A)") (class "Default")
      (node (ref "D8") (pin "1") (pinfunction "A_1") (pintype "passive"))
      (node (ref "R17") (pin "2") (pinfunction "2_2") (pintype "passive"))
    )
    (net (code "35") (name "Net-(D9-A)") (class "Default")
      (node (ref "D9") (pin "1") (pinfunction "A_1") (pintype "passive"))
      (node (ref "R18") (pin "2") (pinfunction "2_2") (pintype "passive"))
    )
    (net (code "36") (name "Net-(D10-A)") (class "Default")
      (node (ref "D10") (pin "1") (pinfunction "A_1") (pintype "passive"))
      (node (ref "R19") (pin "2") (pinfunction "2_2") (pintype "passive"))
    )
    (net (code "37") (name "Net-(D10-K)") (class "Default")
      (node (ref "D10") (pin "2") (pinfunction "K_2") (pintype "passive"))
      (node (ref "D11") (pin "2") (pinfunction "K_2") (pintype "passive"))
      (node (ref "D12") (pin "2") (pinfunction "K_2") (pintype "passive"))
      (node (ref "D5") (pin "2") (pinfunction "K_2") (pintype "passive"))
      (node (ref "D6") (pin "2") (pinfunction "K_2") (pintype "passive"))
      (node (ref "D7") (pin "2") (pinfunction "K_2") (pintype "passive"))
      (node (ref "D8") (pin "2") (pinfunction "K_2") (pintype "passive"))
      (node (ref "D9") (pin "2") (pinfunction "K_2") (pintype "passive"))
      (node (ref "Q5") (pin "1") (pinfunction "D_1") (pintype "passive"))
    )
    (net (code "38") (name "Net-(D11-A)") (class "Default")
      (node (ref "D11") (pin "1") (pinfunction "A_1") (pintype "passive"))
      (node (ref "R20") (pin "2") (pinfunction "2_2") (pintype "passive"))
    )
    (net (code "39") (name "Net-(D12-A)") (class "Default")
      (node (ref "D12") (pin "1") (pinfunction "A_1") (pintype "passive"))
      (node (ref "R21") (pin "2") (pinfunction "2_2") (pintype "passive"))
    )
    (net (code "40") (name "Net-(Header1-CH_PD)") (class "Default")
      (node (ref "Header1") (pin "7") (pinfunction "CH_PD_7") (pintype "passive"))
      (node (ref "R12") (pin "1") (pinfunction "1_1") (pintype "passive"))
    )
    (net (code "41") (name "Net-(Header1-GPIO0)") (class "Default")
      (node (ref "Header1") (pin "3") (pinfunction "GPIO0_3") (pintype "passive"))
      (node (ref "R13") (pin "2") (pinfunction "2_2") (pintype "passive"))
    )
    (net (code "42") (name "Net-(Q1-D)") (class "Default")
      (node (ref "MG1") (pin "2") (pinfunction "2_2") (pintype "passive"))
      (node (ref "Q1") (pin "1") (pinfunction "D_1") (pintype "passive"))
    )
    (net (code "43") (name "Net-(Q1-G)") (class "Default")
      (node (ref "Q1") (pin "2") (pinfunction "G_2") (pintype "passive"))
      (node (ref "R22") (pin "1") (pinfunction "1_1") (pintype "passive"))
    )
    (net (code "44") (name "Net-(Q2-D)") (class "Default")
      (node (ref "MG2") (pin "2") (pinfunction "2_2") (pintype "passive"))
      (node (ref "Q2") (pin "1") (pinfunction "D_1") (pintype "passive"))
    )
    (net (code "45") (name "Net-(Q2-G)") (class "Default")
      (node (ref "Q2") (pin "2") (pinfunction "G_2") (pintype "passive"))
      (node (ref "R23") (pin "1") (pinfunction "1_1") (pintype "passive"))
    )
    (net (code "46") (name "Net-(Q3-D)") (class "Default")
      (node (ref "MG3") (pin "2") (pinfunction "2_2") (pintype "passive"))
      (node (ref "Q3") (pin "1") (pinfunction "D_1") (pintype "passive"))
    )
    (net (code "47") (name "Net-(Q3-G)") (class "Default")
      (node (ref "Q3") (pin "2") (pinfunction "G_2") (pintype "passive"))
      (node (ref "R24") (pin "1") (pinfunction "1_1") (pintype "passive"))
    )
    (net (code "48") (name "Net-(Q4-D)") (class "Default")
      (node (ref "MG4") (pin "2") (pinfunction "2_2") (pintype "passive"))
      (node (ref "Q4") (pin "1") (pinfunction "D_1") (pintype "passive"))
    )
    (net (code "49") (name "Net-(Q4-G)") (class "Default")
      (node (ref "Q4") (pin "2") (pinfunction "G_2") (pintype "passive"))
      (node (ref "R25") (pin "1") (pinfunction "1_1") (pintype "passive"))
    )
    (net (code "50") (name "Net-(Q5-G)") (class "Default")
      (node (ref "Q5") (pin "2") (pinfunction "G_2") (pintype "passive"))
      (node (ref "R30") (pin "1") (pinfunction "1_1") (pintype "passive"))
    )
    (net (code "51") (name "Net-(U1-BOOT0)") (class "Default")
      (node (ref "R4") (pin "2") (pinfunction "2_2") (pintype "passive"))
      (node (ref "U1") (pin "44") (pinfunction "BOOT0_44") (pintype "passive"))
    )
    (net (code "52") (name "Net-(U1-PA4{slash}ADC123_IN4{slash}DAC_OUT1{slash}SPI1_NSS)") (class "Default")
      (node (ref "R1") (pin "1") (pinfunction "1_1") (pintype "passive"))
      (node (ref "R3") (pin "1") (pinfunction "1_1") (pintype "passive"))
      (node (ref "U1") (pin "14") (pinfunction "PA4/ADC123_IN4/DAC_OUT1/SPI1_NSS_14") (pintype "passive"))
    )
    (net (code "53") (name "Net-(U1-PB2{slash}BOOT1)") (class "Default")
      (node (ref "R6") (pin "2") (pinfunction "2_2") (pintype "passive"))
      (node (ref "U1") (pin "20") (pinfunction "PB2/BOOT1_20") (pintype "passive"))
    )
    (net (code "54") (name "Net-(U2-CPOUT)") (class "Default")
      (node (ref "C3") (pin "2") (pinfunction "2_2") (pintype "passive"))
      (node (ref "U2") (pin "20") (pinfunction "CPOUT_20") (pintype "passive"))
    )
    (net (code "55") (name "Net-(U2-FSYNC)") (class "Default")
      (node (ref "C12") (pin "1") (pinfunction "1_1") (pintype "passive"))
      (node (ref "U2") (pin "11") (pinfunction "FSYNC_11") (pintype "passive"))
    )
    (net (code "56") (name "Net-(U3-BYP)") (class "Default")
      (node (ref "C7") (pin "1") (pinfunction "1_1") (pintype "passive"))
      (node (ref "U3") (pin "4") (pinfunction "BYP_4") (pintype "passive"))
    )
    (net (code "57") (name "Net-(U3-EN)") (class "Default")
      (node (ref "C4") (pin "1") (pinfunction "1_1") (pintype "passive"))
      (node (ref "C5") (pin "1") (pinfunction "1_1") (pintype "passive"))
      (node (ref "L1") (pin "2") (pinfunction "2_2") (pintype "passive"))
      (node (ref "U3") (pin "1") (pinfunction "IN_1") (pintype "passive"))
      (node (ref "U3") (pin "3") (pinfunction "EN_3") (pintype "passive"))
    )
    (net (code "58") (name "VCC") (class "Default")
      (node (ref "L2") (pin "2") (pinfunction "2_2") (pintype "passive"))
      (node (ref "R1") (pin "2") (pinfunction "2_2") (pintype "passive"))
      (node (ref "S1") (pin "1") (pinfunction "NC1_1") (pintype "passive"))
    )
    (net (code "59") (name "unconnected-(Header1-GPIO2-Pad2)") (class "Default")
      (node (ref "Header1") (pin "2") (pinfunction "GPIO2_2") (pintype "passive"))
    )
    (net (code "60") (name "unconnected-(Header1-RST-Pad6)") (class "Default")
      (node (ref "Header1") (pin "6") (pinfunction "RST_6") (pintype "passive"))
    )
    (net (code "61") (name "unconnected-(S1-COMMON2-Pad5)") (class "Default")
      (node (ref "S1") (pin "5") (pinfunction "COMMON2_5") (pintype "passive"))
    )
    (net (code "62") (name "unconnected-(S1-NC2-Pad4)") (class "Default")
      (node (ref "S1") (pin "4") (pinfunction "NC2_4") (pintype "passive"))
    )
    (net (code "63") (name "unconnected-(S1-NO1-Pad3)") (class "Default")
      (node (ref "S1") (pin "3") (pinfunction "NO1_3") (pintype "passive"))
    )
    (net (code "64") (name "unconnected-(S1-NO2-Pad6)") (class "Default")
      (node (ref "S1") (pin "6") (pinfunction "NO2_6") (pintype "passive"))
    )
    (net (code "65") (name "unconnected-(U1-PA7{slash}ADC123_IN7{slash}SPI1_MOSI{slash}T8C1N{slash}T3C2{slash}T1C1N-Pad17)") (class "Default")
      (node (ref "U1") (pin "17") (pinfunction "PA7/ADC123_IN7/SPI1_MOSI/T8C1N/T3C2/T1C1N_17") (pintype "passive"))
    )
    (net (code "66") (name "unconnected-(U1-PA8{slash}T1C1{slash}MCO-Pad29)") (class "Default")
      (node (ref "U1") (pin "29") (pinfunction "PA8/T1C1/MCO_29") (pintype "passive"))
    )
    (net (code "67") (name "unconnected-(U1-PA9{slash}T1C2{slash}USART1_Tx-Pad30)") (class "Default")
      (node (ref "U1") (pin "30") (pinfunction "PA9/T1C2/USART1_Tx_30") (pintype "passive"))
    )
    (net (code "68") (name "unconnected-(U1-PA10{slash}T1C3{slash}USART1_Rx-Pad31)") (class "Default")
      (node (ref "U1") (pin "31") (pinfunction "PA10/T1C3/USART1_Rx_31") (pintype "passive"))
    )
    (net (code "69") (name "unconnected-(U1-PA11{slash}CAN_Rx{slash}T1C4{slash}USBDM-Pad32)") (class "Default")
      (node (ref "U1") (pin "32") (pinfunction "PA11/CAN_Rx/T1C4/USBDM_32") (pintype "passive"))
    )
    (net (code "70") (name "unconnected-(U1-PA12{slash}CAN_Tx{slash}T1ETR{slash}USBDP-Pad33)") (class "Default")
      (node (ref "U1") (pin "33") (pinfunction "PA12/CAN_Tx/T1ETR/USBDP_33") (pintype "passive"))
    )
    (net (code "71") (name "unconnected-(U1-PA15{slash}JTDI{slash}I2S3_WS{slash}JTDI{slash}T2C1ETR{slash}SPI3_NSS-Pad38)") (class "Default")
      (node (ref "U1") (pin "38") (pinfunction "PA15/JTDI/I2S3_WS/JTDI/T2C1ETR/SPI3_NSS_38") (pintype "passive"))
    )
    (net (code "72") (name "unconnected-(U1-PB0{slash}ADC123_IN8{slash}T3C3{slash}T8C2N{slash}T1C2N-Pad18)") (class "Default")
      (node (ref "U1") (pin "18") (pinfunction "PB0/ADC123_IN8/T3C3/T8C2N/T1C2N_18") (pintype "passive"))
    )
    (net (code "73") (name "unconnected-(U1-PB1{slash}ADC123_IN9{slash}T3C4{slash}T8C3N{slash}T1C3N-Pad19)") (class "Default")
      (node (ref "U1") (pin "19") (pinfunction "PB1/ADC123_IN9/T3C4/T8C3N/T1C3N_19") (pintype "passive"))
    )
    (net (code "74") (name "unconnected-(U1-PB3{slash}JTDO{slash}SPI3_SCK{slash}I2S3_CK{slash}T2C2{slash}SPI1_SCK-Pad39)") (class "Default")
      (node (ref "U1") (pin "39") (pinfunction "PB3/JTDO/SPI3_SCK/I2S3_CK/T2C2/SPI1_SCK_39") (pintype "passive"))
    )
    (net (code "75") (name "unconnected-(U1-PB4{slash}NJTRST{slash}SPI3_MISO{slash}T3C1{slash}SPI1_MISO-Pad40)") (class "Default")
      (node (ref "U1") (pin "40") (pinfunction "PB4/NJTRST/SPI3_MISO/T3C1/SPI1_MISO_40") (pintype "passive"))
    )
    (net (code "76") (name "unconnected-(U1-PB9{slash}SDIO_D5{slash}I2C1_SDA{slash}T4C4{slash}CAN_Tx-Pad46)") (class "Default")
      (node (ref "U1") (pin "46") (pinfunction "PB9/SDIO_D5/I2C1_SDA/T4C4/CAN_Tx_46") (pintype "passive"))
    )
    (net (code "77") (name "unconnected-(U1-PB12{slash}I2S2_WS{slash}T1BKIN{slash}SPI2_NSS{slash}I2C2_SMBA-Pad25)") (class "Default")
      (node (ref "U1") (pin "25") (pinfunction "PB12/I2S2_WS/T1BKIN/SPI2_NSS/I2C2_SMBA_25") (pintype "passive"))
    )
    (net (code "78") (name "unconnected-(U1-PB13{slash}I2S2_CK{slash}T1CH1N{slash}SPI2_SCK-Pad26)") (class "Default")
      (node (ref "U1") (pin "26") (pinfunction "PB13/I2S2_CK/T1CH1N/SPI2_SCK_26") (pintype "passive"))
    )
    (net (code "79") (name "unconnected-(U1-PB14{slash}T1CH2N{slash}SPI2_MISO-Pad27)") (class "Default")
      (node (ref "U1") (pin "27") (pinfunction "PB14/T1CH2N/SPI2_MISO_27") (pintype "passive"))
    )
    (net (code "80") (name "unconnected-(U1-PB15{slash}I2S2_SD{slash}T1CH3N{slash}SPI2_MOSI-Pad28)") (class "Default")
      (node (ref "U1") (pin "28") (pinfunction "PB15/I2S2_SD/T1CH3N/SPI2_MOSI_28") (pintype "passive"))
    )
    (net (code "81") (name "unconnected-(U1-PC13-TAMPER-RTC-Pad2)") (class "Default")
      (node (ref "U1") (pin "2") (pinfunction "PC13-TAMPER-RTC_2") (pintype "passive"))
    )
    (net (code "82") (name "unconnected-(U1-PC14-OSC32_IN-Pad3)") (class "Default")
      (node (ref "U1") (pin "3") (pinfunction "PC14-OSC32_IN_3") (pintype "passive"))
    )
    (net (code "83") (name "unconnected-(U1-PC15-OSC32_OUT-Pad4)") (class "Default")
      (node (ref "U1") (pin "4") (pinfunction "PC15-OSC32_OUT_4") (pintype "passive"))
    )
    (net (code "84") (name "unconnected-(U2-CL-Pad7)") (class "Default")
      (node (ref "U2") (pin "7") (pinfunction "CL_7") (pintype "passive"))
    )
    (net (code "85") (name "unconnected-(U2-CLKOUT-Pad22)") (class "Default")
      (node (ref "U2") (pin "22") (pinfunction "CLKOUT_22") (pintype "passive"))
    )
    (net (code "86") (name "unconnected-(U2-DA-Pad6)") (class "Default")
      (node (ref "U2") (pin "6") (pinfunction "DA_6") (pintype "passive"))
    )
    (net (code "87") (name "unconnected-(U2-INT-Pad12)") (class "Default")
      (node (ref "U2") (pin "12") (pinfunction "INT_12") (pintype "passive"))
    )
    (net (code "88") (name "unconnected-(U2-NC-Pad2)") (class "Default")
      (node (ref "U2") (pin "2") (pinfunction "NC_2") (pintype "passive"))
    )
    (net (code "89") (name "unconnected-(U2-NC-Pad3)") (class "Default")
      (node (ref "U2") (pin "3") (pinfunction "NC_3") (pintype "passive"))
    )
    (net (code "90") (name "unconnected-(U2-NC-Pad4)") (class "Default")
      (node (ref "U2") (pin "4") (pinfunction "NC_4") (pintype "passive"))
    )
    (net (code "91") (name "unconnected-(U2-NC-Pad5)") (class "Default")
      (node (ref "U2") (pin "5") (pinfunction "NC_5") (pintype "passive"))
    )
    (net (code "92") (name "unconnected-(U2-NC-Pad14)") (class "Default")
      (node (ref "U2") (pin "14") (pinfunction "NC_14") (pintype "passive"))
    )
    (net (code "93") (name "unconnected-(U2-NC-Pad15)") (class "Default")
      (node (ref "U2") (pin "15") (pinfunction "NC_15") (pintype "passive"))
    )
    (net (code "94") (name "unconnected-(U2-NC-Pad16)") (class "Default")
      (node (ref "U2") (pin "16") (pinfunction "NC_16") (pintype "passive"))
    )
    (net (code "95") (name "unconnected-(U2-NC-Pad17)") (class "Default")
      (node (ref "U2") (pin "17") (pinfunction "NC_17") (pintype "passive"))
    )
    (net (code "96") (name "unconnected-(U2-RESV-Pad19)") (class "Default")
      (node (ref "U2") (pin "19") (pinfunction "RESV_19") (pintype "passive"))
    )
    (net (code "97") (name "unconnected-(U2-RESV-Pad21)") (class "Default")
      (node (ref "U2") (pin "21") (pinfunction "RESV_21") (pintype "passive"))
    )
  )
)
